# StepperBreakout.net
KiCad netlist of a schematic drawn in EAGLE
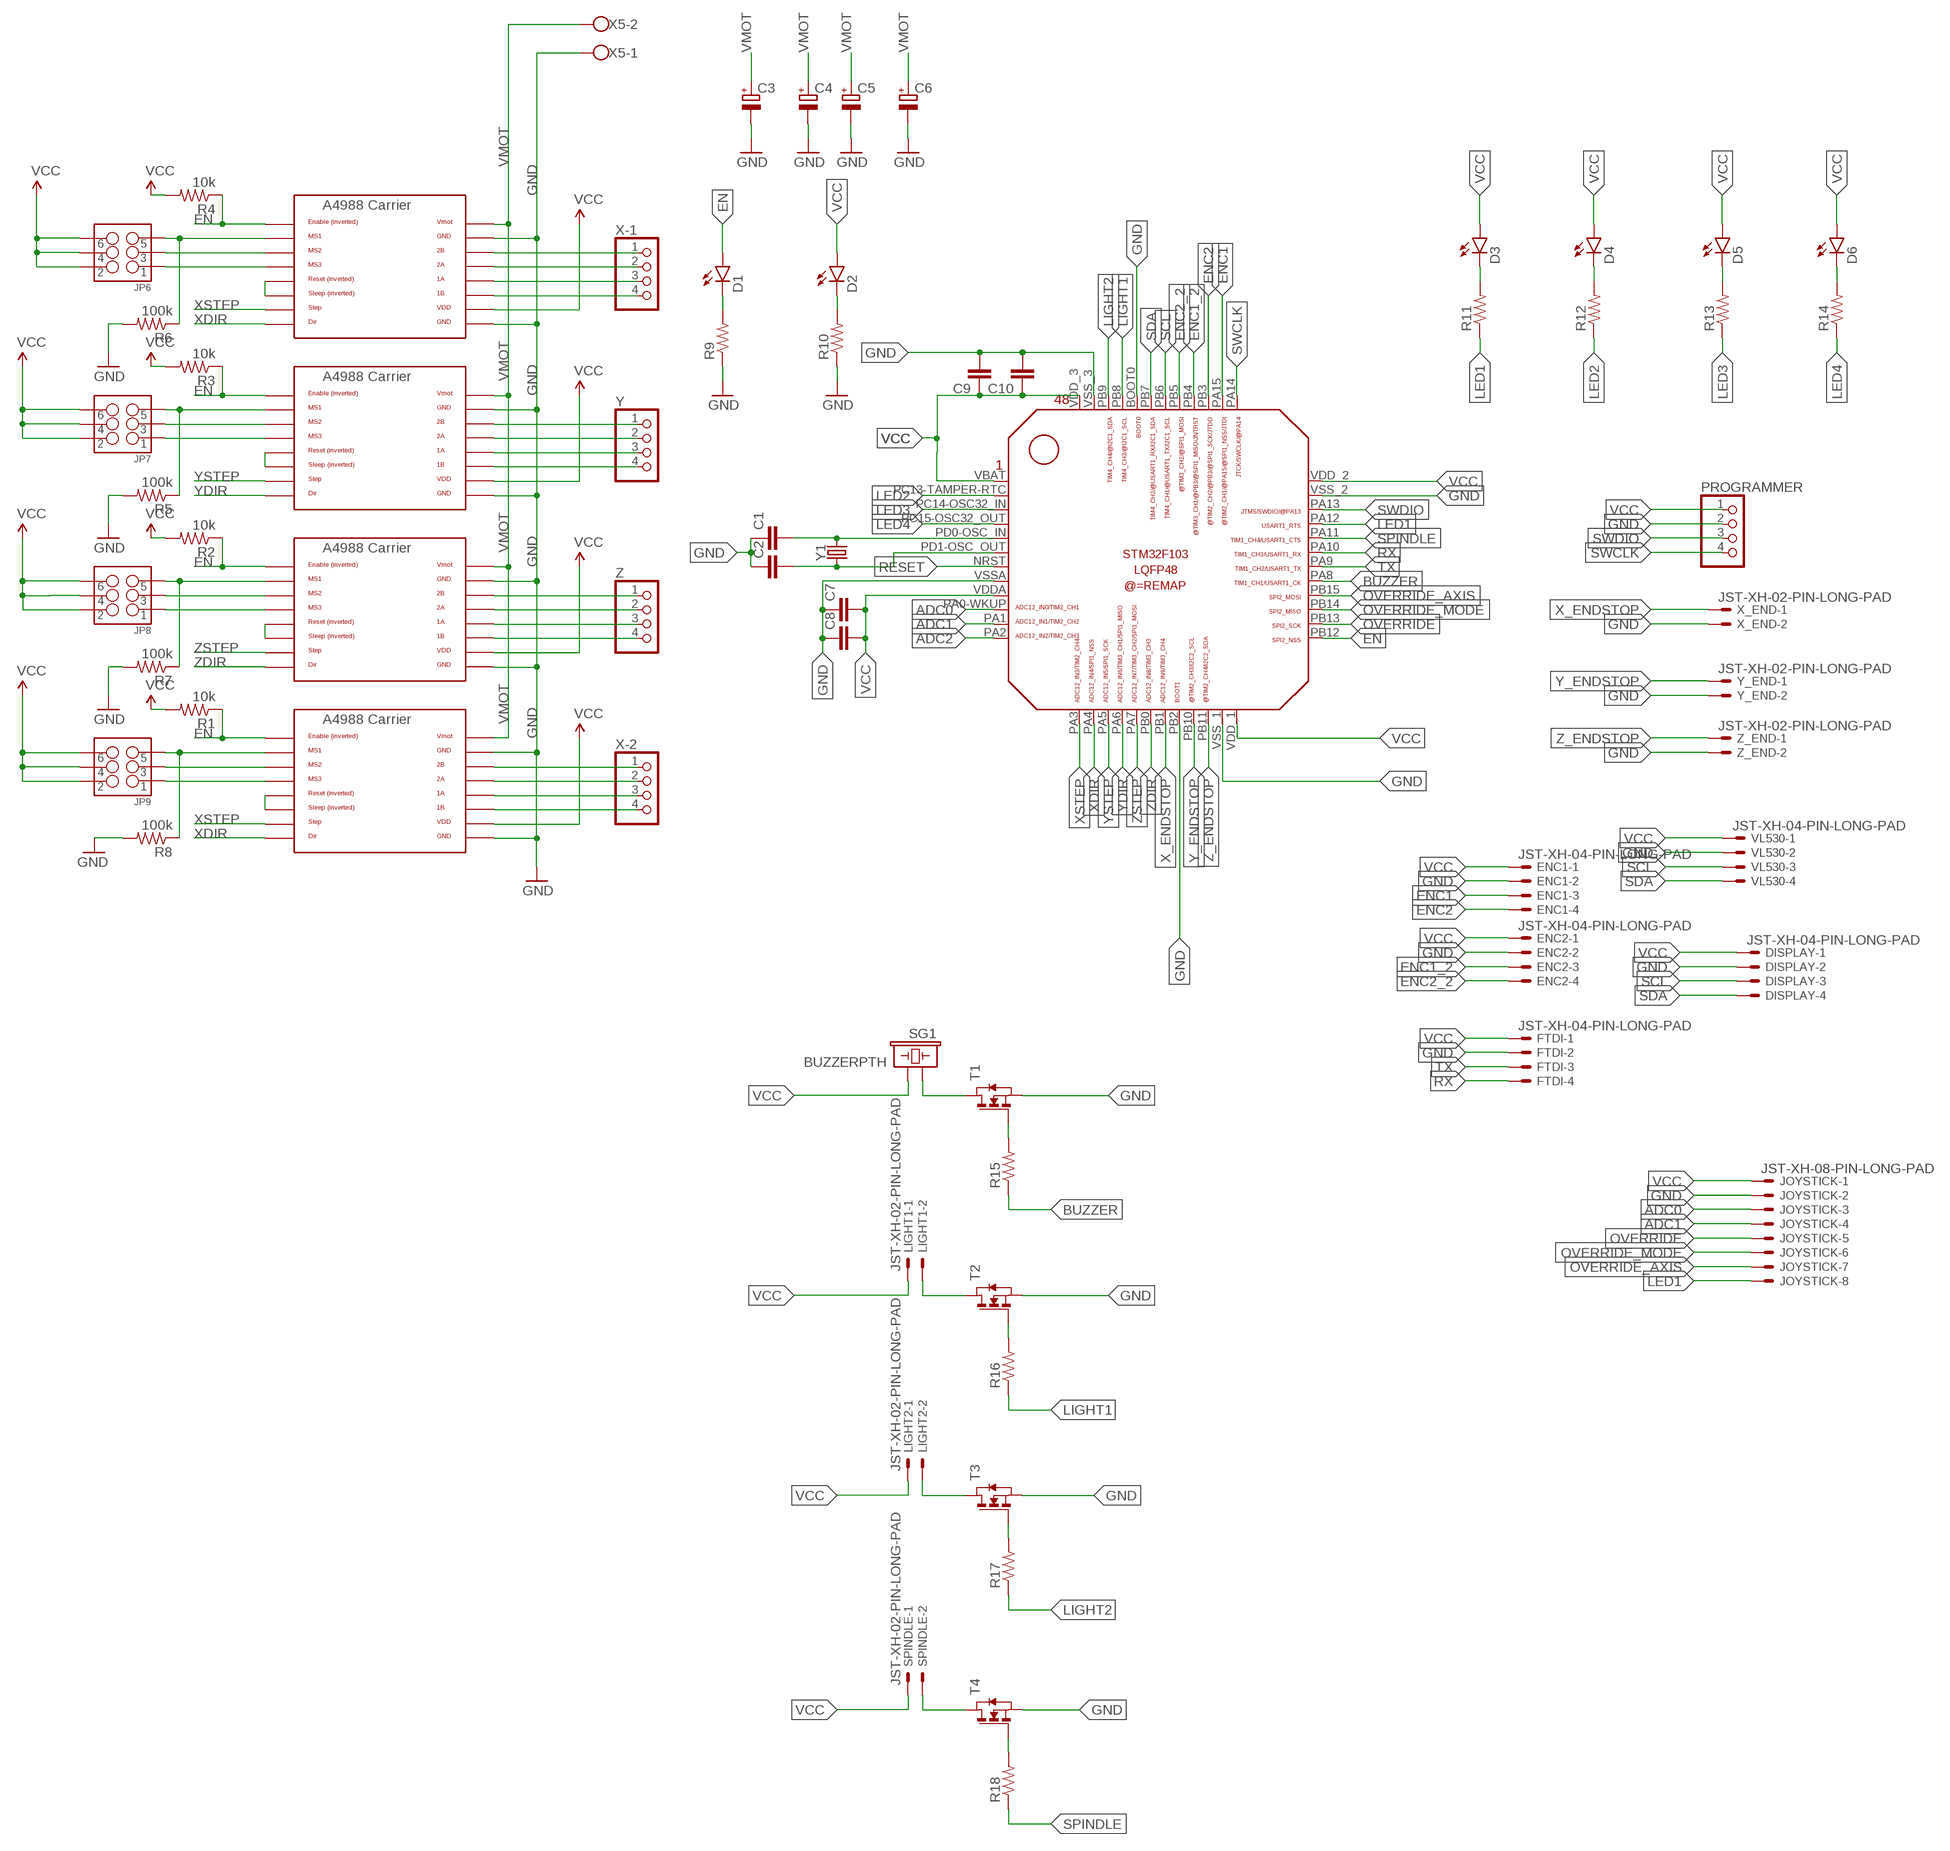
[diagram p0: schematic, sheet 1]

(export (version "E")
  (design (tool "Eeschema 10.0.6"))
  (components
    (comp (ref "C1")
      (value "C-EUC0805")
      (footprint "eagle-import:C0805")
      (libsource (lib "eagle-import") (part "C-EUC0805"))
    )
    (comp (ref "C2")
      (value "C-EUC0805")
      (footprint "eagle-import:C0805")
      (libsource (lib "eagle-import") (part "C-EUC0805"))
    )
    (comp (ref "C3")
      (value "CPOL-EUE5-8.5")
      (footprint "eagle-import:E5-8,5")
      (libsource (lib "eagle-import") (part "CPOL-EUE5-8.5"))
    )
    (comp (ref "C4")
      (value "CPOL-EUE5-8.5")
      (footprint "eagle-import:E5-8,5")
      (libsource (lib "eagle-import") (part "CPOL-EUE5-8.5"))
    )
    (comp (ref "C5")
      (value "CPOL-EUE5-8.5")
      (footprint "eagle-import:E5-8,5")
      (libsource (lib "eagle-import") (part "CPOL-EUE5-8.5"))
    )
    (comp (ref "C6")
      (value "CPOL-EUE5-8.5")
      (footprint "eagle-import:E5-8,5")
      (libsource (lib "eagle-import") (part "CPOL-EUE5-8.5"))
    )
    (comp (ref "C7")
      (value "C-EUC0805")
      (footprint "eagle-import:C0805")
      (libsource (lib "eagle-import") (part "C-EUC0805"))
    )
    (comp (ref "C8")
      (value "C-EUC0805")
      (footprint "eagle-import:C0805")
      (libsource (lib "eagle-import") (part "C-EUC0805"))
    )
    (comp (ref "C9")
      (value "C-EUC0805")
      (footprint "eagle-import:C0805")
      (libsource (lib "eagle-import") (part "C-EUC0805"))
    )
    (comp (ref "C10")
      (value "C-EUC0805")
      (footprint "eagle-import:C0805")
      (libsource (lib "eagle-import") (part "C-EUC0805"))
    )
    (comp (ref "D1")
      (value "LED0603")
      (footprint "eagle-import:LED-0603")
      (libsource (lib "eagle-import") (part "LED0603"))
    )
    (comp (ref "D2")
      (value "LED0603")
      (footprint "eagle-import:LED-0603")
      (libsource (lib "eagle-import") (part "LED0603"))
    )
    (comp (ref "D3")
      (value "LED0603")
      (footprint "eagle-import:LED-0603")
      (libsource (lib "eagle-import") (part "LED0603"))
    )
    (comp (ref "D4")
      (value "LED0603")
      (footprint "eagle-import:LED-0603")
      (libsource (lib "eagle-import") (part "LED0603"))
    )
    (comp (ref "D5")
      (value "LED0603")
      (footprint "eagle-import:LED-0603")
      (libsource (lib "eagle-import") (part "LED0603"))
    )
    (comp (ref "D6")
      (value "LED0603")
      (footprint "eagle-import:LED-0603")
      (libsource (lib "eagle-import") (part "LED0603"))
    )
    (comp (ref "DISPLAY")
      (value "JST-XH-04-PIN-LONG-PAD")
      (footprint "eagle-import:JST-XH-04-PACKAGE-LONG-PAD")
      (libsource (lib "eagle-import") (part "JST-XH-04-PIN-LONG-PAD"))
    )
    (comp (ref "ENC1")
      (value "JST-XH-04-PIN-LONG-PAD")
      (footprint "eagle-import:JST-XH-04-PACKAGE-LONG-PAD")
      (libsource (lib "eagle-import") (part "JST-XH-04-PIN-LONG-PAD"))
    )
    (comp (ref "ENC2")
      (value "JST-XH-04-PIN-LONG-PAD")
      (footprint "eagle-import:JST-XH-04-PACKAGE-LONG-PAD")
      (libsource (lib "eagle-import") (part "JST-XH-04-PIN-LONG-PAD"))
    )
    (comp (ref "FTDI")
      (value "JST-XH-04-PIN-LONG-PAD")
      (footprint "eagle-import:JST-XH-04-PACKAGE-LONG-PAD")
      (libsource (lib "eagle-import") (part "JST-XH-04-PIN-LONG-PAD"))
    )
    (comp (ref "JOYSTICK")
      (value "JST-XH-08-PIN-LONG-PAD")
      (footprint "eagle-import:JST-XH-08-PACKAGE-LONG-PAD")
      (libsource (lib "eagle-import") (part "JST-XH-08-PIN-LONG-PAD"))
    )
    (comp (ref "JP6")
      (value "M03X2NO_SILK")
      (footprint "eagle-import:2X3-NS")
      (libsource (lib "eagle-import") (part "M03X2NO_SILK"))
    )
    (comp (ref "JP7")
      (value "M03X2NO_SILK")
      (footprint "eagle-import:2X3-NS")
      (libsource (lib "eagle-import") (part "M03X2NO_SILK"))
    )
    (comp (ref "JP8")
      (value "M03X2NO_SILK")
      (footprint "eagle-import:2X3-NS")
      (libsource (lib "eagle-import") (part "M03X2NO_SILK"))
    )
    (comp (ref "JP9")
      (value "M03X2NO_SILK")
      (footprint "eagle-import:2X3-NS")
      (libsource (lib "eagle-import") (part "M03X2NO_SILK"))
    )
    (comp (ref "LIGHT1")
      (value "JST-XH-02-PIN-LONG-PAD")
      (footprint "eagle-import:JST-XH-02-PACKAGE-LONG-PAD")
      (libsource (lib "eagle-import") (part "JST-XH-02-PIN-LONG-PAD"))
    )
    (comp (ref "LIGHT2")
      (value "JST-XH-02-PIN-LONG-PAD")
      (footprint "eagle-import:JST-XH-02-PACKAGE-LONG-PAD")
      (libsource (lib "eagle-import") (part "JST-XH-02-PIN-LONG-PAD"))
    )
    (comp (ref "PROGRAMMER")
      (value "PINHD-1X4")
      (footprint "eagle-import:1X04")
      (libsource (lib "eagle-import") (part "PINHD-1X4"))
    )
    (comp (ref "R1")
      (value "10k")
      (footprint "eagle-import:0805")
      (libsource (lib "eagle-import") (part "RESISTOR0805-RES"))
    )
    (comp (ref "R2")
      (value "10k")
      (footprint "eagle-import:0805")
      (libsource (lib "eagle-import") (part "RESISTOR0805-RES"))
    )
    (comp (ref "R3")
      (value "10k")
      (footprint "eagle-import:0805")
      (libsource (lib "eagle-import") (part "RESISTOR0805-RES"))
    )
    (comp (ref "R4")
      (value "10k")
      (footprint "eagle-import:0805")
      (libsource (lib "eagle-import") (part "RESISTOR0805-RES"))
    )
    (comp (ref "R5")
      (value "100k")
      (footprint "eagle-import:0805")
      (libsource (lib "eagle-import") (part "RESISTOR0805-RES"))
    )
    (comp (ref "R6")
      (value "100k")
      (footprint "eagle-import:0805")
      (libsource (lib "eagle-import") (part "RESISTOR0805-RES"))
    )
    (comp (ref "R7")
      (value "100k")
      (footprint "eagle-import:0805")
      (libsource (lib "eagle-import") (part "RESISTOR0805-RES"))
    )
    (comp (ref "R8")
      (value "100k")
      (footprint "eagle-import:0805")
      (libsource (lib "eagle-import") (part "RESISTOR0805-RES"))
    )
    (comp (ref "R9")
      (value "RESISTOR0805-RES")
      (footprint "eagle-import:0805")
      (libsource (lib "eagle-import") (part "SparkFun-Resistors_RESISTOR0805-RES"))
    )
    (comp (ref "R10")
      (value "RESISTOR0805-RES")
      (footprint "eagle-import:0805")
      (libsource (lib "eagle-import") (part "SparkFun-Resistors_RESISTOR0805-RES"))
    )
    (comp (ref "R11")
      (value "RESISTOR0805-RES")
      (footprint "eagle-import:0805")
      (libsource (lib "eagle-import") (part "SparkFun-Resistors_RESISTOR0805-RES"))
    )
    (comp (ref "R12")
      (value "RESISTOR0805-RES")
      (footprint "eagle-import:0805")
      (libsource (lib "eagle-import") (part "SparkFun-Resistors_RESISTOR0805-RES"))
    )
    (comp (ref "R13")
      (value "RESISTOR0805-RES")
      (footprint "eagle-import:0805")
      (libsource (lib "eagle-import") (part "SparkFun-Resistors_RESISTOR0805-RES"))
    )
    (comp (ref "R14")
      (value "RESISTOR0805-RES")
      (footprint "eagle-import:0805")
      (libsource (lib "eagle-import") (part "SparkFun-Resistors_RESISTOR0805-RES"))
    )
    (comp (ref "R15")
      (value "RESISTOR0805-RES")
      (footprint "eagle-import:0805")
      (libsource (lib "eagle-import") (part "SparkFun-Resistors_RESISTOR0805-RES"))
    )
    (comp (ref "R16")
      (value "RESISTOR0805-RES")
      (footprint "eagle-import:0805")
      (libsource (lib "eagle-import") (part "SparkFun-Resistors_RESISTOR0805-RES"))
    )
    (comp (ref "R17")
      (value "RESISTOR0805-RES")
      (footprint "eagle-import:0805")
      (libsource (lib "eagle-import") (part "SparkFun-Resistors_RESISTOR0805-RES"))
    )
    (comp (ref "R18")
      (value "RESISTOR0805-RES")
      (footprint "eagle-import:0805")
      (libsource (lib "eagle-import") (part "SparkFun-Resistors_RESISTOR0805-RES"))
    )
    (comp (ref "SG1")
      (value "BUZZERPTH")
      (footprint "eagle-import:BUZZER-12MM")
      (libsource (lib "eagle-import") (part "BUZZERPTH"))
    )
    (comp (ref "SPINDLE")
      (value "JST-XH-02-PIN-LONG-PAD")
      (footprint "eagle-import:JST-XH-02-PACKAGE-LONG-PAD")
      (libsource (lib "eagle-import") (part "JST-XH-02-PIN-LONG-PAD"))
    )
    (comp (ref "T1")
      (value "NMOSSOT23")
      (footprint "eagle-import:SOT-23")
      (libsource (lib "eagle-import") (part "NMOSSOT23"))
    )
    (comp (ref "T2")
      (value "NMOSSOT23")
      (footprint "eagle-import:SOT-23")
      (libsource (lib "eagle-import") (part "NMOSSOT23"))
    )
    (comp (ref "T3")
      (value "NMOSSOT23")
      (footprint "eagle-import:SOT-23")
      (libsource (lib "eagle-import") (part "NMOSSOT23"))
    )
    (comp (ref "T4")
      (value "NMOSSOT23")
      (footprint "eagle-import:SOT-23")
      (libsource (lib "eagle-import") (part "NMOSSOT23"))
    )
    (comp (ref "U$1")
      (value "POLOLU_A4983CARRIER")
      (footprint "eagle-import:A4988BREAKOUT")
      (libsource (lib "eagle-import") (part "POLOLU_A4983CARRIER"))
    )
    (comp (ref "U$2")
      (value "POLOLU_A4983CARRIER")
      (footprint "eagle-import:A4988BREAKOUT")
      (libsource (lib "eagle-import") (part "POLOLU_A4983CARRIER"))
    )
    (comp (ref "U$3")
      (value "POLOLU_A4983CARRIER")
      (footprint "eagle-import:A4988BREAKOUT")
      (libsource (lib "eagle-import") (part "POLOLU_A4983CARRIER"))
    )
    (comp (ref "U$4")
      (value "POLOLU_A4983CARRIER")
      (footprint "eagle-import:A4988BREAKOUT")
      (libsource (lib "eagle-import") (part "POLOLU_A4983CARRIER"))
    )
    (comp (ref "U$5")
      (value "STM32F103_LQFP48")
      (footprint "eagle-import:STM32F103_LQFP48")
      (libsource (lib "eagle-import") (part "STM32F103_LQFP48"))
    )
    (comp (ref "VL530")
      (value "JST-XH-04-PIN-LONG-PAD")
      (footprint "eagle-import:JST-XH-04-PACKAGE-LONG-PAD")
      (libsource (lib "eagle-import") (part "JST-XH-04-PIN-LONG-PAD"))
    )
    (comp (ref "X-1")
      (value "PINHD-1X4")
      (footprint "eagle-import:1X04")
      (libsource (lib "eagle-import") (part "PINHD-1X4"))
    )
    (comp (ref "X-2")
      (value "PINHD-1X4")
      (footprint "eagle-import:1X04")
      (libsource (lib "eagle-import") (part "PINHD-1X4"))
    )
    (comp (ref "X5")
      (value "W237-102")
      (footprint "eagle-import:W237-102")
      (fields (field (name "MPN") "237-102"))
      (libsource (lib "eagle-import") (part "W237-102"))
    )
    (comp (ref "X_END")
      (value "JST-XH-02-PIN-LONG-PAD")
      (footprint "eagle-import:JST-XH-02-PACKAGE-LONG-PAD")
      (libsource (lib "eagle-import") (part "JST-XH-02-PIN-LONG-PAD"))
    )
    (comp (ref "Y")
      (value "PINHD-1X4")
      (footprint "eagle-import:1X04")
      (libsource (lib "eagle-import") (part "PINHD-1X4"))
    )
    (comp (ref "Y1")
      (value "CRYSTALPTH-HC49UV")
      (footprint "eagle-import:HC49U")
      (libsource (lib "eagle-import") (part "CRYSTALPTH-HC49UV"))
    )
    (comp (ref "Y_END")
      (value "JST-XH-02-PIN-LONG-PAD")
      (footprint "eagle-import:JST-XH-02-PACKAGE-LONG-PAD")
      (libsource (lib "eagle-import") (part "JST-XH-02-PIN-LONG-PAD"))
    )
    (comp (ref "Z")
      (value "PINHD-1X4")
      (footprint "eagle-import:1X04")
      (libsource (lib "eagle-import") (part "PINHD-1X4"))
    )
    (comp (ref "Z_END")
      (value "JST-XH-02-PIN-LONG-PAD")
      (footprint "eagle-import:JST-XH-02-PACKAGE-LONG-PAD")
      (libsource (lib "eagle-import") (part "JST-XH-02-PIN-LONG-PAD"))
    )
  )
  (nets
    (net (code "1") (name "/VMOT") (class "Default")
      (node (ref "C3") (pin "+") (pinfunction "+_+") (pintype "passive"))
      (node (ref "C4") (pin "+") (pinfunction "+_+") (pintype "passive"))
      (node (ref "C5") (pin "+") (pinfunction "+_+") (pintype "passive"))
      (node (ref "C6") (pin "+") (pinfunction "+_+") (pintype "passive"))
      (node (ref "U$1") (pin "VMOT") (pinfunction "VMOT_VMOT") (pintype "power_in"))
      (node (ref "U$2") (pin "VMOT") (pinfunction "VMOT_VMOT") (pintype "power_in"))
      (node (ref "U$3") (pin "VMOT") (pinfunction "VMOT_VMOT") (pintype "power_in"))
      (node (ref "U$4") (pin "VMOT") (pinfunction "VMOT_VMOT") (pintype "power_in"))
      (node (ref "X5") (pin "2") (pinfunction "KL_2") (pintype "passive"))
    )
    (net (code "2") (name "ADC0") (class "Default")
      (node (ref "JOYSTICK") (pin "3") (pinfunction "S_3") (pintype "passive"))
      (node (ref "U$5") (pin "PA0-WKUP") (pinfunction "PA0-WKUP_PA0-WKUP") (pintype "bidirectional"))
    )
    (net (code "3") (name "ADC1") (class "Default")
      (node (ref "JOYSTICK") (pin "4") (pinfunction "S_4") (pintype "passive"))
      (node (ref "U$5") (pin "PA1") (pinfunction "PA1_PA1") (pintype "bidirectional"))
    )
    (net (code "4") (name "ADC2") (class "Default")
      (node (ref "U$5") (pin "PA2") (pinfunction "PA2_PA2") (pintype "bidirectional"))
    )
    (net (code "5") (name "BUZZER") (class "Default")
      (node (ref "R15") (pin "1") (pinfunction "1_1") (pintype "passive"))
      (node (ref "U$5") (pin "PA8") (pinfunction "PA8_PA8") (pintype "bidirectional"))
    )
    (net (code "6") (name "EN") (class "Default")
      (node (ref "D1") (pin "A") (pinfunction "A_A") (pintype "passive"))
      (node (ref "R1") (pin "1") (pinfunction "1_1") (pintype "passive"))
      (node (ref "R2") (pin "1") (pinfunction "1_1") (pintype "passive"))
      (node (ref "R3") (pin "1") (pinfunction "1_1") (pintype "passive"))
      (node (ref "R4") (pin "1") (pinfunction "1_1") (pintype "passive"))
      (node (ref "U$1") (pin "EN") (pinfunction "EN_EN") (pintype "input"))
      (node (ref "U$2") (pin "EN") (pinfunction "EN_EN") (pintype "input"))
      (node (ref "U$3") (pin "EN") (pinfunction "EN_EN") (pintype "input"))
      (node (ref "U$4") (pin "EN") (pinfunction "EN_EN") (pintype "input"))
      (node (ref "U$5") (pin "PB12") (pinfunction "PB12_PB12") (pintype "bidirectional"))
    )
    (net (code "7") (name "ENC1") (class "Default")
      (node (ref "ENC1") (pin "3") (pinfunction "S_3") (pintype "passive"))
      (node (ref "U$5") (pin "PA15") (pinfunction "PA15_PA15") (pintype "bidirectional"))
    )
    (net (code "8") (name "ENC1_2") (class "Default")
      (node (ref "ENC2") (pin "3") (pinfunction "S_3") (pintype "passive"))
      (node (ref "U$5") (pin "PB4") (pinfunction "PB4_PB4") (pintype "bidirectional"))
    )
    (net (code "9") (name "ENC2") (class "Default")
      (node (ref "ENC1") (pin "4") (pinfunction "S_4") (pintype "passive"))
      (node (ref "U$5") (pin "PB3") (pinfunction "PB3_PB3") (pintype "bidirectional"))
    )
    (net (code "10") (name "ENC2_2") (class "Default")
      (node (ref "ENC2") (pin "4") (pinfunction "S_4") (pintype "passive"))
      (node (ref "U$5") (pin "PB5") (pinfunction "PB5_PB5") (pintype "bidirectional"))
    )
    (net (code "11") (name "GND") (class "Default")
      (node (ref "C1") (pin "1") (pinfunction "1_1") (pintype "passive"))
      (node (ref "C10") (pin "2") (pinfunction "2_2") (pintype "passive"))
      (node (ref "C2") (pin "1") (pinfunction "1_1") (pintype "passive"))
      (node (ref "C3") (pin "-") (pinfunction "-_-") (pintype "passive"))
      (node (ref "C4") (pin "-") (pinfunction "-_-") (pintype "passive"))
      (node (ref "C5") (pin "-") (pinfunction "-_-") (pintype "passive"))
      (node (ref "C6") (pin "-") (pinfunction "-_-") (pintype "passive"))
      (node (ref "C7") (pin "1") (pinfunction "1_1") (pintype "passive"))
      (node (ref "C8") (pin "1") (pinfunction "1_1") (pintype "passive"))
      (node (ref "C9") (pin "2") (pinfunction "2_2") (pintype "passive"))
      (node (ref "DISPLAY") (pin "2") (pinfunction "S_2") (pintype "passive"))
      (node (ref "ENC1") (pin "2") (pinfunction "S_2") (pintype "passive"))
      (node (ref "ENC2") (pin "2") (pinfunction "S_2") (pintype "passive"))
      (node (ref "FTDI") (pin "2") (pinfunction "S_2") (pintype "passive"))
      (node (ref "JOYSTICK") (pin "2") (pinfunction "S_2") (pintype "passive"))
      (node (ref "PROGRAMMER") (pin "2") (pinfunction "2_2") (pintype "passive"))
      (node (ref "R10") (pin "1") (pinfunction "1_1") (pintype "passive"))
      (node (ref "R5") (pin "2") (pinfunction "2_2") (pintype "passive"))
      (node (ref "R6") (pin "2") (pinfunction "2_2") (pintype "passive"))
      (node (ref "R7") (pin "2") (pinfunction "2_2") (pintype "passive"))
      (node (ref "R8") (pin "2") (pinfunction "2_2") (pintype "passive"))
      (node (ref "R9") (pin "1") (pinfunction "1_1") (pintype "passive"))
      (node (ref "T1") (pin "2") (pinfunction "S_2") (pintype "passive"))
      (node (ref "T2") (pin "2") (pinfunction "S_2") (pintype "passive"))
      (node (ref "T3") (pin "2") (pinfunction "S_2") (pintype "passive"))
      (node (ref "T4") (pin "2") (pinfunction "S_2") (pintype "passive"))
      (node (ref "U$1") (pin "GND") (pinfunction "GND_GND") (pintype "power_in"))
      (node (ref "U$1") (pin "GND@0") (pinfunction "GND_GND@0") (pintype "power_in"))
      (node (ref "U$2") (pin "GND") (pinfunction "GND_GND") (pintype "power_in"))
      (node (ref "U$2") (pin "GND@0") (pinfunction "GND_GND@0") (pintype "power_in"))
      (node (ref "U$3") (pin "GND") (pinfunction "GND_GND") (pintype "power_in"))
      (node (ref "U$3") (pin "GND@0") (pinfunction "GND_GND@0") (pintype "power_in"))
      (node (ref "U$4") (pin "GND") (pinfunction "GND_GND") (pintype "power_in"))
      (node (ref "U$4") (pin "GND@0") (pinfunction "GND_GND@0") (pintype "power_in"))
      (node (ref "U$5") (pin "BOOT0") (pinfunction "BOOT0_BOOT0") (pintype "bidirectional"))
      (node (ref "U$5") (pin "PB2") (pinfunction "PB2_PB2") (pintype "bidirectional"))
      (node (ref "U$5") (pin "VSSA") (pinfunction "VSSA_VSSA") (pintype "bidirectional"))
      (node (ref "U$5") (pin "VSS_1") (pinfunction "VSS_1_VSS_1") (pintype "bidirectional"))
      (node (ref "U$5") (pin "VSS_2") (pinfunction "VSS_2_VSS_2") (pintype "bidirectional"))
      (node (ref "U$5") (pin "VSS_3") (pinfunction "VSS_3_VSS_3") (pintype "bidirectional"))
      (node (ref "VL530") (pin "2") (pinfunction "S_2") (pintype "passive"))
      (node (ref "X5") (pin "1") (pinfunction "KL_1") (pintype "passive"))
      (node (ref "X_END") (pin "2") (pinfunction "S_2") (pintype "passive"))
      (node (ref "Y_END") (pin "2") (pinfunction "S_2") (pintype "passive"))
      (node (ref "Z_END") (pin "2") (pinfunction "S_2") (pintype "passive"))
    )
    (net (code "12") (name "LED1") (class "Default")
      (node (ref "JOYSTICK") (pin "8") (pinfunction "S_8") (pintype "passive"))
      (node (ref "R11") (pin "1") (pinfunction "1_1") (pintype "passive"))
      (node (ref "U$5") (pin "PA12") (pinfunction "PA12_PA12") (pintype "bidirectional"))
    )
    (net (code "13") (name "LED2") (class "Default")
      (node (ref "R12") (pin "1") (pinfunction "1_1") (pintype "passive"))
      (node (ref "U$5") (pin "PC13-TAMPER-RTC") (pinfunction "PC13-TAMPER-RTC_PC13-TAMPER-RTC") (pintype "bidirectional"))
    )
    (net (code "14") (name "LED3") (class "Default")
      (node (ref "R13") (pin "1") (pinfunction "1_1") (pintype "passive"))
      (node (ref "U$5") (pin "PC14-OSC32_IN") (pinfunction "PC14-OSC32_IN_PC14-OSC32_IN") (pintype "bidirectional"))
    )
    (net (code "15") (name "LED4") (class "Default")
      (node (ref "R14") (pin "1") (pinfunction "1_1") (pintype "passive"))
      (node (ref "U$5") (pin "PC15-OSC32_OUT") (pinfunction "PC15-OSC_OUT_PC15-OSC32_OUT") (pintype "bidirectional"))
    )
    (net (code "16") (name "LIGHT1") (class "Default")
      (node (ref "R16") (pin "1") (pinfunction "1_1") (pintype "passive"))
      (node (ref "U$5") (pin "PB8") (pinfunction "PB8_PB8") (pintype "bidirectional"))
    )
    (net (code "17") (name "LIGHT2") (class "Default")
      (node (ref "R17") (pin "1") (pinfunction "1_1") (pintype "passive"))
      (node (ref "U$5") (pin "PB9") (pinfunction "PB9_PB9") (pintype "bidirectional"))
    )
    (net (code "18") (name "Net-(C1-Pad2)") (class "Default")
      (node (ref "C1") (pin "2") (pinfunction "2_2") (pintype "passive"))
      (node (ref "U$5") (pin "PD0-OSC_IN") (pinfunction "PD0-OSC_IN_PD0-OSC_IN") (pintype "bidirectional"))
      (node (ref "Y1") (pin "2") (pinfunction "2_2") (pintype "passive"))
    )
    (net (code "19") (name "Net-(C2-Pad2)") (class "Default")
      (node (ref "C2") (pin "2") (pinfunction "2_2") (pintype "passive"))
      (node (ref "U$5") (pin "PD1-OSC_OUT") (pinfunction "PD1-OSC_OUT_PD1-OSC_OUT") (pintype "bidirectional"))
      (node (ref "Y1") (pin "1") (pinfunction "1_1") (pintype "passive"))
    )
    (net (code "20") (name "Net-(D1-PadC)") (class "Default")
      (node (ref "D1") (pin "C") (pinfunction "C_C") (pintype "passive"))
      (node (ref "R9") (pin "2") (pinfunction "2_2") (pintype "passive"))
    )
    (net (code "21") (name "Net-(D2-PadC)") (class "Default")
      (node (ref "D2") (pin "C") (pinfunction "C_C") (pintype "passive"))
      (node (ref "R10") (pin "2") (pinfunction "2_2") (pintype "passive"))
    )
    (net (code "22") (name "Net-(D3-PadC)") (class "Default")
      (node (ref "D3") (pin "C") (pinfunction "C_C") (pintype "passive"))
      (node (ref "R11") (pin "2") (pinfunction "2_2") (pintype "passive"))
    )
    (net (code "23") (name "Net-(D4-PadC)") (class "Default")
      (node (ref "D4") (pin "C") (pinfunction "C_C") (pintype "passive"))
      (node (ref "R12") (pin "2") (pinfunction "2_2") (pintype "passive"))
    )
    (net (code "24") (name "Net-(D5-PadC)") (class "Default")
      (node (ref "D5") (pin "C") (pinfunction "C_C") (pintype "passive"))
      (node (ref "R13") (pin "2") (pinfunction "2_2") (pintype "passive"))
    )
    (net (code "25") (name "Net-(D6-PadC)") (class "Default")
      (node (ref "D6") (pin "C") (pinfunction "C_C") (pintype "passive"))
      (node (ref "R14") (pin "2") (pinfunction "2_2") (pintype "passive"))
    )
    (net (code "26") (name "Net-(JP6-Pad1)") (class "Default")
      (node (ref "JP6") (pin "1") (pinfunction "1_1") (pintype "bidirectional"))
      (node (ref "U$4") (pin "MS3") (pinfunction "MS3_MS3") (pintype "input"))
    )
    (net (code "27") (name "Net-(JP6-Pad3)") (class "Default")
      (node (ref "JP6") (pin "3") (pinfunction "3_3") (pintype "bidirectional"))
      (node (ref "U$4") (pin "MS2") (pinfunction "MS2_MS2") (pintype "input"))
    )
    (net (code "28") (name "Net-(JP6-Pad5)") (class "Default")
      (node (ref "JP6") (pin "5") (pinfunction "5_5") (pintype "bidirectional"))
      (node (ref "R6") (pin "1") (pinfunction "1_1") (pintype "passive"))
      (node (ref "U$4") (pin "MS1") (pinfunction "MS1_MS1") (pintype "input"))
    )
    (net (code "29") (name "Net-(JP7-Pad1)") (class "Default")
      (node (ref "JP7") (pin "1") (pinfunction "1_1") (pintype "bidirectional"))
      (node (ref "U$3") (pin "MS3") (pinfunction "MS3_MS3") (pintype "input"))
    )
    (net (code "30") (name "Net-(JP7-Pad3)") (class "Default")
      (node (ref "JP7") (pin "3") (pinfunction "3_3") (pintype "bidirectional"))
      (node (ref "U$3") (pin "MS2") (pinfunction "MS2_MS2") (pintype "input"))
    )
    (net (code "31") (name "Net-(JP7-Pad5)") (class "Default")
      (node (ref "JP7") (pin "5") (pinfunction "5_5") (pintype "bidirectional"))
      (node (ref "R5") (pin "1") (pinfunction "1_1") (pintype "passive"))
      (node (ref "U$3") (pin "MS1") (pinfunction "MS1_MS1") (pintype "input"))
    )
    (net (code "32") (name "Net-(JP8-Pad1)") (class "Default")
      (node (ref "JP8") (pin "1") (pinfunction "1_1") (pintype "bidirectional"))
      (node (ref "U$1") (pin "MS3") (pinfunction "MS3_MS3") (pintype "input"))
    )
    (net (code "33") (name "Net-(JP8-Pad3)") (class "Default")
      (node (ref "JP8") (pin "3") (pinfunction "3_3") (pintype "bidirectional"))
      (node (ref "U$1") (pin "MS2") (pinfunction "MS2_MS2") (pintype "input"))
    )
    (net (code "34") (name "Net-(JP8-Pad5)") (class "Default")
      (node (ref "JP8") (pin "5") (pinfunction "5_5") (pintype "bidirectional"))
      (node (ref "R7") (pin "1") (pinfunction "1_1") (pintype "passive"))
      (node (ref "U$1") (pin "MS1") (pinfunction "MS1_MS1") (pintype "input"))
    )
    (net (code "35") (name "Net-(JP9-Pad1)") (class "Default")
      (node (ref "JP9") (pin "1") (pinfunction "1_1") (pintype "bidirectional"))
      (node (ref "U$2") (pin "MS3") (pinfunction "MS3_MS3") (pintype "input"))
    )
    (net (code "36") (name "Net-(JP9-Pad3)") (class "Default")
      (node (ref "JP9") (pin "3") (pinfunction "3_3") (pintype "bidirectional"))
      (node (ref "U$2") (pin "MS2") (pinfunction "MS2_MS2") (pintype "input"))
    )
    (net (code "37") (name "Net-(JP9-Pad5)") (class "Default")
      (node (ref "JP9") (pin "5") (pinfunction "5_5") (pintype "bidirectional"))
      (node (ref "R8") (pin "1") (pinfunction "1_1") (pintype "passive"))
      (node (ref "U$2") (pin "MS1") (pinfunction "MS1_MS1") (pintype "input"))
    )
    (net (code "38") (name "Net-(LIGHT1B-S)") (class "Default")
      (node (ref "LIGHT1") (pin "2") (pinfunction "S_2") (pintype "passive"))
      (node (ref "T2") (pin "1") (pinfunction "D_1") (pintype "passive"))
    )
    (net (code "39") (name "Net-(LIGHT2B-S)") (class "Default")
      (node (ref "LIGHT2") (pin "2") (pinfunction "S_2") (pintype "passive"))
      (node (ref "T3") (pin "1") (pinfunction "D_1") (pintype "passive"))
    )
    (net (code "40") (name "Net-(SG1-1)") (class "Default")
      (node (ref "SG1") (pin "+") (pinfunction "1_+") (pintype "passive"))
      (node (ref "T1") (pin "1") (pinfunction "D_1") (pintype "passive"))
    )
    (net (code "41") (name "Net-(SPINDLEB-S)") (class "Default")
      (node (ref "SPINDLE") (pin "2") (pinfunction "S_2") (pintype "passive"))
      (node (ref "T4") (pin "1") (pinfunction "D_1") (pintype "passive"))
    )
    (net (code "42") (name "Net-(T1-G)") (class "Default")
      (node (ref "R15") (pin "2") (pinfunction "2_2") (pintype "passive"))
      (node (ref "T1") (pin "3") (pinfunction "G_3") (pintype "passive"))
    )
    (net (code "43") (name "Net-(T2-G)") (class "Default")
      (node (ref "R16") (pin "2") (pinfunction "2_2") (pintype "passive"))
      (node (ref "T2") (pin "3") (pinfunction "G_3") (pintype "passive"))
    )
    (net (code "44") (name "Net-(T3-G)") (class "Default")
      (node (ref "R17") (pin "2") (pinfunction "2_2") (pintype "passive"))
      (node (ref "T3") (pin "3") (pinfunction "G_3") (pintype "passive"))
    )
    (net (code "45") (name "Net-(T4-G)") (class "Default")
      (node (ref "R18") (pin "2") (pinfunction "2_2") (pintype "passive"))
      (node (ref "T4") (pin "3") (pinfunction "G_3") (pintype "passive"))
    )
    (net (code "46") (name "Net-(U$1-Pad1A)") (class "Default")
      (node (ref "U$1") (pin "1A") (pinfunction "1A_1A") (pintype "output"))
      (node (ref "Z") (pin "3") (pinfunction "3_3") (pintype "passive"))
    )
    (net (code "47") (name "Net-(U$1-Pad1B)") (class "Default")
      (node (ref "U$1") (pin "1B") (pinfunction "1B_1B") (pintype "output"))
      (node (ref "Z") (pin "4") (pinfunction "4_4") (pintype "passive"))
    )
    (net (code "48") (name "Net-(U$1-Pad2A)") (class "Default")
      (node (ref "U$1") (pin "2A") (pinfunction "2A_2A") (pintype "output"))
      (node (ref "Z") (pin "2") (pinfunction "2_2") (pintype "passive"))
    )
    (net (code "49") (name "Net-(U$1-Pad2B)") (class "Default")
      (node (ref "U$1") (pin "2B") (pinfunction "2B_2B") (pintype "output"))
      (node (ref "Z") (pin "1") (pinfunction "1_1") (pintype "passive"))
    )
    (net (code "50") (name "Net-(U$1-SLEEP)") (class "Default")
      (node (ref "U$1") (pin "RST") (pinfunction "RST_RST") (pintype "input"))
      (node (ref "U$1") (pin "SLP") (pinfunction "SLEEP_SLP") (pintype "input"))
    )
    (net (code "51") (name "Net-(U$2-Pad1A)") (class "Default")
      (node (ref "U$2") (pin "1A") (pinfunction "1A_1A") (pintype "output"))
      (node (ref "X-2") (pin "3") (pinfunction "3_3") (pintype "passive"))
    )
    (net (code "52") (name "Net-(U$2-Pad1B)") (class "Default")
      (node (ref "U$2") (pin "1B") (pinfunction "1B_1B") (pintype "output"))
      (node (ref "X-2") (pin "4") (pinfunction "4_4") (pintype "passive"))
    )
    (net (code "53") (name "Net-(U$2-Pad2A)") (class "Default")
      (node (ref "U$2") (pin "2A") (pinfunction "2A_2A") (pintype "output"))
      (node (ref "X-2") (pin "2") (pinfunction "2_2") (pintype "passive"))
    )
    (net (code "54") (name "Net-(U$2-Pad2B)") (class "Default")
      (node (ref "U$2") (pin "2B") (pinfunction "2B_2B") (pintype "output"))
      (node (ref "X-2") (pin "1") (pinfunction "1_1") (pintype "passive"))
    )
    (net (code "55") (name "Net-(U$2-SLEEP)") (class "Default")
      (node (ref "U$2") (pin "RST") (pinfunction "RST_RST") (pintype "input"))
      (node (ref "U$2") (pin "SLP") (pinfunction "SLEEP_SLP") (pintype "input"))
    )
    (net (code "56") (name "Net-(U$3-Pad1A)") (class "Default")
      (node (ref "U$3") (pin "1A") (pinfunction "1A_1A") (pintype "output"))
      (node (ref "Y") (pin "3") (pinfunction "3_3") (pintype "passive"))
    )
    (net (code "57") (name "Net-(U$3-Pad1B)") (class "Default")
      (node (ref "U$3") (pin "1B") (pinfunction "1B_1B") (pintype "output"))
      (node (ref "Y") (pin "4") (pinfunction "4_4") (pintype "passive"))
    )
    (net (code "58") (name "Net-(U$3-Pad2A)") (class "Default")
      (node (ref "U$3") (pin "2A") (pinfunction "2A_2A") (pintype "output"))
      (node (ref "Y") (pin "2") (pinfunction "2_2") (pintype "passive"))
    )
    (net (code "59") (name "Net-(U$3-Pad2B)") (class "Default")
      (node (ref "U$3") (pin "2B") (pinfunction "2B_2B") (pintype "output"))
      (node (ref "Y") (pin "1") (pinfunction "1_1") (pintype "passive"))
    )
    (net (code "60") (name "Net-(U$3-SLEEP)") (class "Default")
      (node (ref "U$3") (pin "RST") (pinfunction "RST_RST") (pintype "input"))
      (node (ref "U$3") (pin "SLP") (pinfunction "SLEEP_SLP") (pintype "input"))
    )
    (net (code "61") (name "Net-(U$4-Pad1A)") (class "Default")
      (node (ref "U$4") (pin "1A") (pinfunction "1A_1A") (pintype "output"))
      (node (ref "X-1") (pin "3") (pinfunction "3_3") (pintype "passive"))
    )
    (net (code "62") (name "Net-(U$4-Pad1B)") (class "Default")
      (node (ref "U$4") (pin "1B") (pinfunction "1B_1B") (pintype "output"))
      (node (ref "X-1") (pin "4") (pinfunction "4_4") (pintype "passive"))
    )
    (net (code "63") (name "Net-(U$4-Pad2A)") (class "Default")
      (node (ref "U$4") (pin "2A") (pinfunction "2A_2A") (pintype "output"))
      (node (ref "X-1") (pin "2") (pinfunction "2_2") (pintype "passive"))
    )
    (net (code "64") (name "Net-(U$4-Pad2B)") (class "Default")
      (node (ref "U$4") (pin "2B") (pinfunction "2B_2B") (pintype "output"))
      (node (ref "X-1") (pin "1") (pinfunction "1_1") (pintype "passive"))
    )
    (net (code "65") (name "Net-(U$4-SLEEP)") (class "Default")
      (node (ref "U$4") (pin "RST") (pinfunction "RST_RST") (pintype "input"))
      (node (ref "U$4") (pin "SLP") (pinfunction "SLEEP_SLP") (pintype "input"))
    )
    (net (code "66") (name "OVERRIDE") (class "Default")
      (node (ref "JOYSTICK") (pin "5") (pinfunction "S_5") (pintype "passive"))
      (node (ref "U$5") (pin "PB13") (pinfunction "PB13_PB13") (pintype "bidirectional"))
    )
    (net (code "67") (name "OVERRIDE_AXIS") (class "Default")
      (node (ref "JOYSTICK") (pin "7") (pinfunction "S_7") (pintype "passive"))
      (node (ref "U$5") (pin "PB15") (pinfunction "PB15_PB15") (pintype "bidirectional"))
    )
    (net (code "68") (name "OVERRIDE_MODE") (class "Default")
      (node (ref "JOYSTICK") (pin "6") (pinfunction "S_6") (pintype "passive"))
      (node (ref "U$5") (pin "PB14") (pinfunction "PB14_PB14") (pintype "bidirectional"))
    )
    (net (code "69") (name "RESET") (class "Default")
      (node (ref "U$5") (pin "NRST") (pinfunction "NRST_NRST") (pintype "bidirectional"))
    )
    (net (code "70") (name "RX") (class "Default")
      (node (ref "FTDI") (pin "4") (pinfunction "S_4") (pintype "passive"))
      (node (ref "U$5") (pin "PA10") (pinfunction "PA10_PA10") (pintype "bidirectional"))
    )
    (net (code "71") (name "SCL") (class "Default")
      (node (ref "DISPLAY") (pin "3") (pinfunction "S_3") (pintype "passive"))
      (node (ref "U$5") (pin "PB6") (pinfunction "PB6_PB6") (pintype "bidirectional"))
      (node (ref "VL530") (pin "3") (pinfunction "S_3") (pintype "passive"))
    )
    (net (code "72") (name "SDA") (class "Default")
      (node (ref "DISPLAY") (pin "4") (pinfunction "S_4") (pintype "passive"))
      (node (ref "U$5") (pin "PB7") (pinfunction "PB7_PB7") (pintype "bidirectional"))
      (node (ref "VL530") (pin "4") (pinfunction "S_4") (pintype "passive"))
    )
    (net (code "73") (name "SPINDLE") (class "Default")
      (node (ref "R18") (pin "1") (pinfunction "1_1") (pintype "passive"))
      (node (ref "U$5") (pin "PA11") (pinfunction "PA11_PA11") (pintype "bidirectional"))
    )
    (net (code "74") (name "SWCLK") (class "Default")
      (node (ref "PROGRAMMER") (pin "4") (pinfunction "4_4") (pintype "passive"))
      (node (ref "U$5") (pin "PA14") (pinfunction "PA14_PA14") (pintype "bidirectional"))
    )
    (net (code "75") (name "SWDIO") (class "Default")
      (node (ref "PROGRAMMER") (pin "3") (pinfunction "3_3") (pintype "passive"))
      (node (ref "U$5") (pin "PA13") (pinfunction "PA13_PA13") (pintype "bidirectional"))
    )
    (net (code "76") (name "TX") (class "Default")
      (node (ref "FTDI") (pin "3") (pinfunction "S_3") (pintype "passive"))
      (node (ref "U$5") (pin "PA9") (pinfunction "PA9_PA9") (pintype "bidirectional"))
    )
    (net (code "77") (name "VCC") (class "Default")
      (node (ref "C10") (pin "1") (pinfunction "1_1") (pintype "passive"))
      (node (ref "C7") (pin "2") (pinfunction "2_2") (pintype "passive"))
      (node (ref "C8") (pin "2") (pinfunction "2_2") (pintype "passive"))
      (node (ref "C9") (pin "1") (pinfunction "1_1") (pintype "passive"))
      (node (ref "D2") (pin "A") (pinfunction "A_A") (pintype "passive"))
      (node (ref "D3") (pin "A") (pinfunction "A_A") (pintype "passive"))
      (node (ref "D4") (pin "A") (pinfunction "A_A") (pintype "passive"))
      (node (ref "D5") (pin "A") (pinfunction "A_A") (pintype "passive"))
      (node (ref "D6") (pin "A") (pinfunction "A_A") (pintype "passive"))
      (node (ref "DISPLAY") (pin "1") (pinfunction "S_1") (pintype "passive"))
      (node (ref "ENC1") (pin "1") (pinfunction "S_1") (pintype "passive"))
      (node (ref "ENC2") (pin "1") (pinfunction "S_1") (pintype "passive"))
      (node (ref "FTDI") (pin "1") (pinfunction "S_1") (pintype "passive"))
      (node (ref "JOYSTICK") (pin "1") (pinfunction "S_1") (pintype "passive"))
      (node (ref "JP6") (pin "2") (pinfunction "2_2") (pintype "bidirectional"))
      (node (ref "JP6") (pin "4") (pinfunction "4_4") (pintype "bidirectional"))
      (node (ref "JP6") (pin "6") (pinfunction "6_6") (pintype "bidirectional"))
      (node (ref "JP7") (pin "2") (pinfunction "2_2") (pintype "bidirectional"))
      (node (ref "JP7") (pin "4") (pinfunction "4_4") (pintype "bidirectional"))
      (node (ref "JP7") (pin "6") (pinfunction "6_6") (pintype "bidirectional"))
      (node (ref "JP8") (pin "2") (pinfunction "2_2") (pintype "bidirectional"))
      (node (ref "JP8") (pin "4") (pinfunction "4_4") (pintype "bidirectional"))
      (node (ref "JP8") (pin "6") (pinfunction "6_6") (pintype "bidirectional"))
      (node (ref "JP9") (pin "2") (pinfunction "2_2") (pintype "bidirectional"))
      (node (ref "JP9") (pin "4") (pinfunction "4_4") (pintype "bidirectional"))
      (node (ref "JP9") (pin "6") (pinfunction "6_6") (pintype "bidirectional"))
      (node (ref "LIGHT1") (pin "1") (pinfunction "S_1") (pintype "passive"))
      (node (ref "LIGHT2") (pin "1") (pinfunction "S_1") (pintype "passive"))
      (node (ref "PROGRAMMER") (pin "1") (pinfunction "1_1") (pintype "passive"))
      (node (ref "R1") (pin "2") (pinfunction "2_2") (pintype "passive"))
      (node (ref "R2") (pin "2") (pinfunction "2_2") (pintype "passive"))
      (node (ref "R3") (pin "2") (pinfunction "2_2") (pintype "passive"))
      (node (ref "R4") (pin "2") (pinfunction "2_2") (pintype "passive"))
      (node (ref "SG1") (pin "-") (pinfunction "2_-") (pintype "passive"))
      (node (ref "SPINDLE") (pin "1") (pinfunction "S_1") (pintype "passive"))
      (node (ref "U$1") (pin "VDD") (pinfunction "VDD_VDD") (pintype "power_in"))
      (node (ref "U$2") (pin "VDD") (pinfunction "VDD_VDD") (pintype "power_in"))
      (node (ref "U$3") (pin "VDD") (pinfunction "VDD_VDD") (pintype "power_in"))
      (node (ref "U$4") (pin "VDD") (pinfunction "VDD_VDD") (pintype "power_in"))
      (node (ref "U$5") (pin "VBAT") (pinfunction "VBAT_VBAT") (pintype "bidirectional"))
      (node (ref "U$5") (pin "VDDA") (pinfunction "VDDA_VDDA") (pintype "bidirectional"))
      (node (ref "U$5") (pin "VDD_1") (pinfunction "VDD_1_VDD_1") (pintype "bidirectional"))
      (node (ref "U$5") (pin "VDD_2") (pinfunction "VDD_2_VDD_2") (pintype "bidirectional"))
      (node (ref "U$5") (pin "VDD_3") (pinfunction "VDD_3_VDD_3") (pintype "bidirectional"))
      (node (ref "VL530") (pin "1") (pinfunction "S_1") (pintype "passive"))
    )
    (net (code "78") (name "XDIR") (class "Default")
      (node (ref "U$2") (pin "DIR") (pinfunction "DIR_DIR") (pintype "input"))
      (node (ref "U$4") (pin "DIR") (pinfunction "DIR_DIR") (pintype "input"))
      (node (ref "U$5") (pin "PA4") (pinfunction "PA4_PA4") (pintype "bidirectional"))
    )
    (net (code "79") (name "XSTEP") (class "Default")
      (node (ref "U$2") (pin "STEP") (pinfunction "STEP_STEP") (pintype "input"))
      (node (ref "U$4") (pin "STEP") (pinfunction "STEP_STEP") (pintype "input"))
      (node (ref "U$5") (pin "PA3") (pinfunction "PA3_PA3") (pintype "bidirectional"))
    )
    (net (code "80") (name "X_ENDSTOP") (class "Default")
      (node (ref "U$5") (pin "PB1") (pinfunction "PB1_PB1") (pintype "bidirectional"))
      (node (ref "X_END") (pin "1") (pinfunction "S_1") (pintype "passive"))
    )
    (net (code "81") (name "YDIR") (class "Default")
      (node (ref "U$3") (pin "DIR") (pinfunction "DIR_DIR") (pintype "input"))
      (node (ref "U$5") (pin "PA6") (pinfunction "PA6_PA6") (pintype "bidirectional"))
    )
    (net (code "82") (name "YSTEP") (class "Default")
      (node (ref "U$3") (pin "STEP") (pinfunction "STEP_STEP") (pintype "input"))
      (node (ref "U$5") (pin "PA5") (pinfunction "PA5_PA5") (pintype "bidirectional"))
    )
    (net (code "83") (name "Y_ENDSTOP") (class "Default")
      (node (ref "U$5") (pin "PB10") (pinfunction "PB10_PB10") (pintype "bidirectional"))
      (node (ref "Y_END") (pin "1") (pinfunction "S_1") (pintype "passive"))
    )
    (net (code "84") (name "ZDIR") (class "Default")
      (node (ref "U$1") (pin "DIR") (pinfunction "DIR_DIR") (pintype "input"))
      (node (ref "U$5") (pin "PB0") (pinfunction "PB0_PB0") (pintype "bidirectional"))
    )
    (net (code "85") (name "ZSTEP") (class "Default")
      (node (ref "U$1") (pin "STEP") (pinfunction "STEP_STEP") (pintype "input"))
      (node (ref "U$5") (pin "PA7") (pinfunction "PA7_PA7") (pintype "bidirectional"))
    )
    (net (code "86") (name "Z_ENDSTOP") (class "Default")
      (node (ref "U$5") (pin "PB11") (pinfunction "PB11_PB11") (pintype "bidirectional"))
      (node (ref "Z_END") (pin "1") (pinfunction "S_1") (pintype "passive"))
    )
  )
)
